# Prototipo_2_1.net
KiCad netlist of a schematic drawn in EAGLE
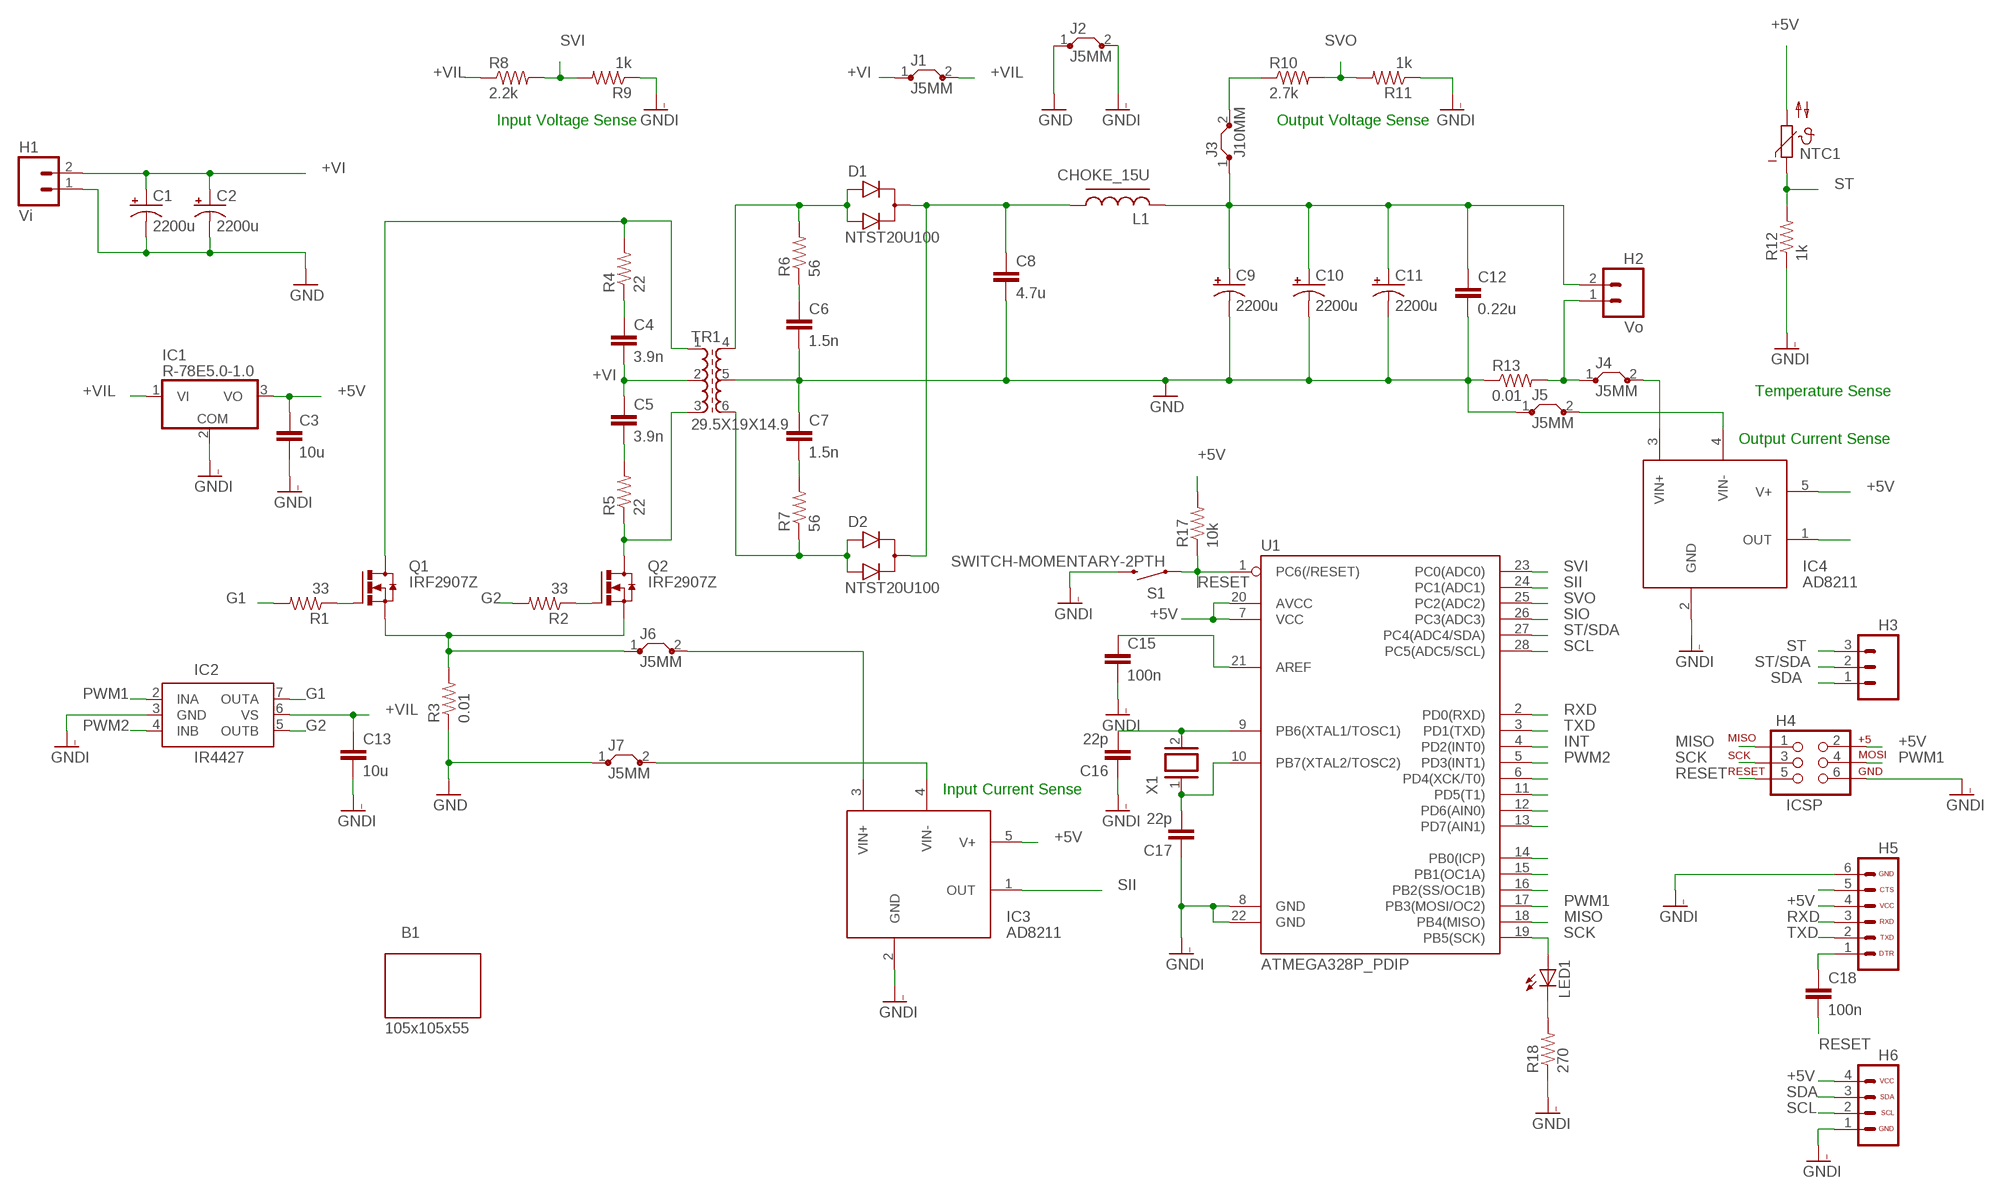
[diagram p0: schematic, sheet 1]

(export (version "E")
  (design (tool "Eeschema 10.0.6"))
  (components
    (comp (ref "B1")
      (value "105x105x55")
      (footprint "eagle-import:BOX_105X105X55")
      (libsource (lib "eagle-import") (part "BOX_105X105X55"))
    )
    (comp (ref "C1")
      (value "2200u")
      (footprint "eagle-import:CPOL_RADIAL_12.5MM_5MM")
      (libsource (lib "eagle-import") (part "CPOL_12.5MM_5MM"))
    )
    (comp (ref "C2")
      (value "2200u")
      (footprint "eagle-import:CPOL_RADIAL_12.5MM_5MM")
      (libsource (lib "eagle-import") (part "CPOL_12.5MM_5MM"))
    )
    (comp (ref "C3")
      (value "10u")
      (footprint "eagle-import:C5B2.5")
      (libsource (lib "eagle-import") (part "C5/2.5"))
    )
    (comp (ref "C4")
      (value "3.9n")
      (footprint "eagle-import:C7.5B3")
      (libsource (lib "eagle-import") (part "C7.5/3"))
    )
    (comp (ref "C5")
      (value "3.9n")
      (footprint "eagle-import:C7.5B3")
      (libsource (lib "eagle-import") (part "C7.5/3"))
    )
    (comp (ref "C6")
      (value "1.5n")
      (footprint "eagle-import:C7.5B3")
      (libsource (lib "eagle-import") (part "C7.5/3"))
    )
    (comp (ref "C7")
      (value "1.5n")
      (footprint "eagle-import:C7.5B3")
      (libsource (lib "eagle-import") (part "C7.5/3"))
    )
    (comp (ref "C8")
      (value "4.7u")
      (footprint "eagle-import:C5B2.5")
      (libsource (lib "eagle-import") (part "C5/2.5"))
    )
    (comp (ref "C9")
      (value "2200u")
      (footprint "eagle-import:CPOL_RADIAL_12.5MM_5MM")
      (libsource (lib "eagle-import") (part "CPOL_12.5MM_5MM"))
    )
    (comp (ref "C10")
      (value "2200u")
      (footprint "eagle-import:CPOL_RADIAL_12.5MM_5MM")
      (libsource (lib "eagle-import") (part "CPOL_12.5MM_5MM"))
    )
    (comp (ref "C11")
      (value "2200u")
      (footprint "eagle-import:CPOL_RADIAL_12.5MM_5MM")
      (libsource (lib "eagle-import") (part "CPOL_12.5MM_5MM"))
    )
    (comp (ref "C12")
      (value "0.22u")
      (footprint "eagle-import:C5B3")
      (libsource (lib "eagle-import") (part "C5/3"))
    )
    (comp (ref "C13")
      (value "10u")
      (footprint "eagle-import:C5B2.5")
      (libsource (lib "eagle-import") (part "C5/2.5"))
    )
    (comp (ref "C15")
      (value "100n")
      (footprint "eagle-import:C5B3")
      (libsource (lib "eagle-import") (part "C5/3"))
    )
    (comp (ref "C16")
      (value "22p")
      (footprint "eagle-import:C5B2.5")
      (libsource (lib "eagle-import") (part "C5/2.5"))
    )
    (comp (ref "C17")
      (value "22p")
      (footprint "eagle-import:C5B2.5")
      (libsource (lib "eagle-import") (part "C5/2.5"))
    )
    (comp (ref "C18")
      (value "100n")
      (footprint "eagle-import:C5B3")
      (libsource (lib "eagle-import") (part "C5/3"))
    )
    (comp (ref "D1")
      (value "NTST20U100")
      (footprint "eagle-import:TO220V")
      (libsource (lib "eagle-import") (part "NTST20U100CTG"))
    )
    (comp (ref "D2")
      (value "NTST20U100")
      (footprint "eagle-import:TO220V")
      (libsource (lib "eagle-import") (part "NTST20U100CTG"))
    )
    (comp (ref "H1")
      (value "Vi")
      (footprint "eagle-import:SCREWTERMINAL-5MM-2")
      (libsource (lib "eagle-import") (part "M025MM"))
    )
    (comp (ref "H2")
      (value "Vo")
      (footprint "eagle-import:SCREWTERMINAL-5MM-2")
      (libsource (lib "eagle-import") (part "M025MM"))
    )
    (comp (ref "H3")
      (value "M03PTH")
      (footprint "eagle-import:1X03")
      (libsource (lib "eagle-import") (part "M03PTH"))
    )
    (comp (ref "H4")
      (value "ICSP")
      (footprint "eagle-import:2X3")
      (libsource (lib "eagle-import") (part "AVR_SPI_PRG_6PTH"))
    )
    (comp (ref "H5")
      (value "HEADER_SERIAL")
      (footprint "eagle-import:HEADER_SERIAL")
      (libsource (lib "eagle-import") (part "HEADER_SERIAL"))
    )
    (comp (ref "H6")
      (value "HEADER_I2C")
      (footprint "eagle-import:HEADER_I2C")
      (libsource (lib "eagle-import") (part "HEADER_I2C"))
    )
    (comp (ref "IC1")
      (value "R-78E5.0-1.0")
      (footprint "eagle-import:R-78E5.0-1.0")
      (libsource (lib "eagle-import") (part "R-78E5.0-1.0"))
    )
    (comp (ref "IC2")
      (value "IR4427")
      (footprint "eagle-import:DIL08")
      (libsource (lib "eagle-import") (part "IR4427"))
    )
    (comp (ref "IC3")
      (value "AD8211")
      (footprint "eagle-import:RJ-5")
      (libsource (lib "eagle-import") (part "AD8211"))
    )
    (comp (ref "IC4")
      (value "AD8211")
      (footprint "eagle-import:RJ-5")
      (libsource (lib "eagle-import") (part "AD8211"))
    )
    (comp (ref "J1")
      (value "J5MM")
      (footprint "eagle-import:05")
      (libsource (lib "eagle-import") (part "J5MM"))
    )
    (comp (ref "J2")
      (value "J5MM")
      (footprint "eagle-import:05")
      (libsource (lib "eagle-import") (part "J5MM"))
    )
    (comp (ref "J3")
      (value "J10MM")
      (footprint "eagle-import:10")
      (libsource (lib "eagle-import") (part "J10MM"))
    )
    (comp (ref "J4")
      (value "J5MM")
      (footprint "eagle-import:05")
      (libsource (lib "eagle-import") (part "J5MM"))
    )
    (comp (ref "J5")
      (value "J5MM")
      (footprint "eagle-import:05")
      (libsource (lib "eagle-import") (part "J5MM"))
    )
    (comp (ref "J6")
      (value "J5MM")
      (footprint "eagle-import:05")
      (libsource (lib "eagle-import") (part "J5MM"))
    )
    (comp (ref "J7")
      (value "J5MM")
      (footprint "eagle-import:05")
      (libsource (lib "eagle-import") (part "J5MM"))
    )
    (comp (ref "L1")
      (value "CHOKE_15U")
      (footprint "eagle-import:CHOKE_15U")
      (libsource (lib "eagle-import") (part "CHOKE_15U"))
    )
    (comp (ref "LED1")
      (value "LED5MM")
      (footprint "eagle-import:LED5MM")
      (libsource (lib "eagle-import") (part "LED5MM"))
    )
    (comp (ref "NTC1")
      (value "NTC640")
      (footprint "eagle-import:P640")
      (fields (field (name "OC_FARNELL") "unknown") (field (name "OC_NEWARK") "unknown"))
      (libsource (lib "eagle-import") (part "NTC640"))
    )
    (comp (ref "Q1")
      (value "IRF2907Z")
      (footprint "eagle-import:TO220V")
      (libsource (lib "eagle-import") (part "IRF2907Z"))
    )
    (comp (ref "Q2")
      (value "IRF2907Z")
      (footprint "eagle-import:TO220V")
      (libsource (lib "eagle-import") (part "IRF2907Z"))
    )
    (comp (ref "R1")
      (value "33")
      (footprint "eagle-import:AXIAL-0.4")
      (libsource (lib "eagle-import") (part "RESISTORPTH-1/4W"))
    )
    (comp (ref "R2")
      (value "33")
      (footprint "eagle-import:AXIAL-0.4")
      (libsource (lib "eagle-import") (part "RESISTORPTH-1/4W"))
    )
    (comp (ref "R3")
      (value "0.01")
      (footprint "eagle-import:RSENSE")
      (libsource (lib "eagle-import") (part "RSENSE"))
    )
    (comp (ref "R4")
      (value "22")
      (footprint "eagle-import:AXIAL-0.5")
      (libsource (lib "eagle-import") (part "RESISTORPTH-1/2W"))
    )
    (comp (ref "R5")
      (value "22")
      (footprint "eagle-import:AXIAL-0.5")
      (libsource (lib "eagle-import") (part "RESISTORPTH-1/2W"))
    )
    (comp (ref "R6")
      (value "56")
      (footprint "eagle-import:AXIAL-0.5")
      (libsource (lib "eagle-import") (part "RESISTORPTH-1/2W"))
    )
    (comp (ref "R7")
      (value "56")
      (footprint "eagle-import:AXIAL-0.5")
      (libsource (lib "eagle-import") (part "RESISTORPTH-1/2W"))
    )
    (comp (ref "R8")
      (value "2.2k")
      (footprint "eagle-import:AXIAL-0.4")
      (libsource (lib "eagle-import") (part "RESISTORPTH-1/4W"))
    )
    (comp (ref "R9")
      (value "1k")
      (footprint "eagle-import:AXIAL-0.4")
      (libsource (lib "eagle-import") (part "RESISTORPTH-1/4W"))
    )
    (comp (ref "R10")
      (value "2.7k")
      (footprint "eagle-import:AXIAL-0.4")
      (libsource (lib "eagle-import") (part "RESISTORPTH-1/4W"))
    )
    (comp (ref "R11")
      (value "1k")
      (footprint "eagle-import:AXIAL-0.4")
      (libsource (lib "eagle-import") (part "RESISTORPTH-1/4W"))
    )
    (comp (ref "R12")
      (value "1k")
      (footprint "eagle-import:AXIAL-0.4")
      (libsource (lib "eagle-import") (part "RESISTORPTH-1/4W"))
    )
    (comp (ref "R13")
      (value "0.01")
      (footprint "eagle-import:RSENSE")
      (libsource (lib "eagle-import") (part "RSENSE"))
    )
    (comp (ref "R17")
      (value "10k")
      (footprint "eagle-import:AXIAL-0.4")
      (libsource (lib "eagle-import") (part "RESISTORPTH-1/4W"))
    )
    (comp (ref "R18")
      (value "270")
      (footprint "eagle-import:AXIAL-0.4")
      (libsource (lib "eagle-import") (part "RESISTORPTH-1/4W"))
    )
    (comp (ref "S1")
      (value "SWITCH-MOMENTARY-2PTH")
      (footprint "eagle-import:TACTILE-PTH")
      (libsource (lib "eagle-import") (part "SWITCH-MOMENTARY-2PTH"))
    )
    (comp (ref "TR1")
      (value "29.5X19X14.9")
      (footprint "eagle-import:CORE_29.5X19X14.9")
      (libsource (lib "eagle-import") (part "29.5X19X14.9_N87"))
    )
    (comp (ref "U1")
      (value "ATMEGA328P_PDIP")
      (footprint "eagle-import:DIL28-3")
      (libsource (lib "eagle-import") (part "ATMEGA328P_PDIP"))
    )
    (comp (ref "X1")
      (value "XTAL/S")
      (footprint "eagle-import:QS")
      (libsource (lib "eagle-import") (part "XTAL/S"))
    )
  )
  (nets
    (net (code "1") (name "/+5V") (class "Default")
      (node (ref "C3") (pin "1") (pinfunction "1_1") (pintype "passive"))
      (node (ref "H4") (pin "2") (pinfunction "2_2") (pintype "passive"))
      (node (ref "H5") (pin "4") (pinfunction "4_VCC_4") (pintype "passive"))
      (node (ref "H6") (pin "4") (pinfunction "4_VCC_4") (pintype "passive"))
      (node (ref "IC1") (pin "3") (pinfunction "VO_3") (pintype "power_in"))
      (node (ref "IC3") (pin "5") (pinfunction "V+_5") (pintype "bidirectional"))
      (node (ref "IC4") (pin "5") (pinfunction "V+_5") (pintype "bidirectional"))
      (node (ref "NTC1") (pin "2") (pinfunction "2_2") (pintype "passive"))
      (node (ref "R17") (pin "P$2") (pinfunction "2_P$2") (pintype "passive"))
      (node (ref "U1") (pin "20") (pinfunction "AVCC_20") (pintype "bidirectional"))
      (node (ref "U1") (pin "7") (pinfunction "VCC_7") (pintype "bidirectional"))
    )
    (net (code "2") (name "/+VI") (class "Default")
      (node (ref "C1") (pin "+") (pinfunction "+_+") (pintype "passive"))
      (node (ref "C2") (pin "+") (pinfunction "+_+") (pintype "passive"))
      (node (ref "C4") (pin "2") (pinfunction "2_2") (pintype "passive"))
      (node (ref "C5") (pin "1") (pinfunction "1_1") (pintype "passive"))
      (node (ref "H1") (pin "2") (pinfunction "2_2") (pintype "passive"))
      (node (ref "J1") (pin "1") (pinfunction "1_1") (pintype "passive"))
      (node (ref "TR1") (pin "2") (pinfunction "2_2") (pintype "passive"))
    )
    (net (code "3") (name "/+VIL") (class "Default")
      (node (ref "C13") (pin "1") (pinfunction "1_1") (pintype "passive"))
      (node (ref "IC1") (pin "1") (pinfunction "VI_1") (pintype "power_in"))
      (node (ref "IC2") (pin "6") (pinfunction "VS_6") (pintype "bidirectional"))
      (node (ref "J1") (pin "2") (pinfunction "2_2") (pintype "passive"))
      (node (ref "R8") (pin "P$1") (pinfunction "1_P$1") (pintype "passive"))
    )
    (net (code "4") (name "/G1") (class "Default")
      (node (ref "IC2") (pin "7") (pinfunction "OUTA_7") (pintype "bidirectional"))
      (node (ref "R1") (pin "P$2") (pinfunction "2_P$2") (pintype "passive"))
    )
    (net (code "5") (name "/G2") (class "Default")
      (node (ref "IC2") (pin "5") (pinfunction "OUTB_5") (pintype "bidirectional"))
      (node (ref "R2") (pin "P$2") (pinfunction "2_P$2") (pintype "passive"))
    )
    (net (code "6") (name "/INT") (class "Default")
      (node (ref "U1") (pin "4") (pinfunction "PD2(INT0)_4") (pintype "bidirectional"))
    )
    (net (code "7") (name "/MISO") (class "Default")
      (node (ref "H4") (pin "1") (pinfunction "1_1") (pintype "passive"))
      (node (ref "U1") (pin "18") (pinfunction "PB4(MISO)_18") (pintype "bidirectional"))
    )
    (net (code "8") (name "/PWM1") (class "Default")
      (node (ref "H4") (pin "4") (pinfunction "4_4") (pintype "passive"))
      (node (ref "IC2") (pin "2") (pinfunction "INA_2") (pintype "bidirectional"))
      (node (ref "U1") (pin "17") (pinfunction "PB3(MOSI/OC2)_17") (pintype "bidirectional"))
    )
    (net (code "9") (name "/PWM2") (class "Default")
      (node (ref "IC2") (pin "4") (pinfunction "INB_4") (pintype "bidirectional"))
      (node (ref "U1") (pin "5") (pinfunction "PD3(INT1)_5") (pintype "bidirectional"))
    )
    (net (code "10") (name "/RESET") (class "Default")
      (node (ref "C18") (pin "2") (pinfunction "2_2") (pintype "passive"))
      (node (ref "H4") (pin "5") (pinfunction "5_5") (pintype "passive"))
      (node (ref "R17") (pin "P$1") (pinfunction "1_P$1") (pintype "passive"))
      (node (ref "S1") (pin "1") (pinfunction "1_1") (pintype "passive"))
      (node (ref "U1") (pin "1") (pinfunction "PC6(/RESET)_1") (pintype "bidirectional"))
    )
    (net (code "11") (name "/RXD") (class "Default")
      (node (ref "H5") (pin "3") (pinfunction "3_RXD_3") (pintype "passive"))
      (node (ref "U1") (pin "2") (pinfunction "PD0(RXD)_2") (pintype "bidirectional"))
    )
    (net (code "12") (name "/SCK") (class "Default")
      (node (ref "H4") (pin "3") (pinfunction "3_3") (pintype "passive"))
      (node (ref "LED1") (pin "A") (pinfunction "A_A") (pintype "passive"))
      (node (ref "U1") (pin "19") (pinfunction "PB5(SCK)_19") (pintype "bidirectional"))
    )
    (net (code "13") (name "/SCL") (class "Default")
      (node (ref "H6") (pin "2") (pinfunction "2_SCL_2") (pintype "passive"))
      (node (ref "U1") (pin "28") (pinfunction "PC5(ADC5/SCL)_28") (pintype "bidirectional"))
    )
    (net (code "14") (name "/SDA") (class "Default")
      (node (ref "H3") (pin "1") (pinfunction "1_1") (pintype "passive"))
      (node (ref "H6") (pin "3") (pinfunction "3_SDA_3") (pintype "passive"))
    )
    (net (code "15") (name "/SII") (class "Default")
      (node (ref "IC3") (pin "1") (pinfunction "OUT_1") (pintype "bidirectional"))
      (node (ref "U1") (pin "24") (pinfunction "PC1(ADC1)_24") (pintype "bidirectional"))
    )
    (net (code "16") (name "/SIO") (class "Default")
      (node (ref "IC4") (pin "1") (pinfunction "OUT_1") (pintype "bidirectional"))
      (node (ref "U1") (pin "26") (pinfunction "PC3(ADC3)_26") (pintype "bidirectional"))
    )
    (net (code "17") (name "/ST") (class "Default")
      (node (ref "H3") (pin "3") (pinfunction "3_3") (pintype "passive"))
      (node (ref "NTC1") (pin "1") (pinfunction "1_1") (pintype "passive"))
      (node (ref "R12") (pin "P$2") (pinfunction "2_P$2") (pintype "passive"))
    )
    (net (code "18") (name "/ST{slash}SDA") (class "Default")
      (node (ref "H3") (pin "2") (pinfunction "2_2") (pintype "passive"))
      (node (ref "U1") (pin "27") (pinfunction "PC4(ADC4/SDA)_27") (pintype "bidirectional"))
    )
    (net (code "19") (name "/SVI") (class "Default")
      (node (ref "R8") (pin "P$2") (pinfunction "2_P$2") (pintype "passive"))
      (node (ref "R9") (pin "P$2") (pinfunction "2_P$2") (pintype "passive"))
      (node (ref "U1") (pin "23") (pinfunction "PC0(ADC0)_23") (pintype "bidirectional"))
    )
    (net (code "20") (name "/SVO") (class "Default")
      (node (ref "R10") (pin "P$2") (pinfunction "2_P$2") (pintype "passive"))
      (node (ref "R11") (pin "P$2") (pinfunction "2_P$2") (pintype "passive"))
      (node (ref "U1") (pin "25") (pinfunction "PC2(ADC2)_25") (pintype "bidirectional"))
    )
    (net (code "21") (name "/TXD") (class "Default")
      (node (ref "H5") (pin "2") (pinfunction "2_TXD_2") (pintype "passive"))
      (node (ref "U1") (pin "3") (pinfunction "PD1(TXD)_3") (pintype "bidirectional"))
    )
    (net (code "22") (name "GND") (class "Default")
      (node (ref "C1") (pin "-") (pinfunction "-_-") (pintype "passive"))
      (node (ref "C10") (pin "-") (pinfunction "-_-") (pintype "passive"))
      (node (ref "C11") (pin "-") (pinfunction "-_-") (pintype "passive"))
      (node (ref "C12") (pin "2") (pinfunction "2_2") (pintype "passive"))
      (node (ref "C2") (pin "-") (pinfunction "-_-") (pintype "passive"))
      (node (ref "C6") (pin "2") (pinfunction "2_2") (pintype "passive"))
      (node (ref "C7") (pin "1") (pinfunction "1_1") (pintype "passive"))
      (node (ref "C8") (pin "2") (pinfunction "2_2") (pintype "passive"))
      (node (ref "C9") (pin "-") (pinfunction "-_-") (pintype "passive"))
      (node (ref "H1") (pin "1") (pinfunction "1_1") (pintype "passive"))
      (node (ref "J2") (pin "1") (pinfunction "1_1") (pintype "passive"))
      (node (ref "J5") (pin "1") (pinfunction "1_1") (pintype "passive"))
      (node (ref "J7") (pin "1") (pinfunction "1_1") (pintype "passive"))
      (node (ref "R13") (pin "P$1") (pinfunction "1_P$1") (pintype "passive"))
      (node (ref "R3") (pin "P$1") (pinfunction "1_P$1") (pintype "passive"))
      (node (ref "TR1") (pin "5") (pinfunction "5_5") (pintype "passive"))
    )
    (net (code "23") (name "GNDI") (class "Default")
      (node (ref "C13") (pin "2") (pinfunction "2_2") (pintype "passive"))
      (node (ref "C15") (pin "2") (pinfunction "2_2") (pintype "passive"))
      (node (ref "C16") (pin "1") (pinfunction "1_1") (pintype "passive"))
      (node (ref "C17") (pin "1") (pinfunction "1_1") (pintype "passive"))
      (node (ref "C3") (pin "2") (pinfunction "2_2") (pintype "passive"))
      (node (ref "H4") (pin "6") (pinfunction "6_6") (pintype "passive"))
      (node (ref "H5") (pin "6") (pinfunction "6_GND_6") (pintype "passive"))
      (node (ref "H6") (pin "1") (pinfunction "1_GND_1") (pintype "passive"))
      (node (ref "IC1") (pin "2") (pinfunction "COM_2") (pintype "power_in"))
      (node (ref "IC2") (pin "3") (pinfunction "GND_3") (pintype "bidirectional"))
      (node (ref "IC3") (pin "2") (pinfunction "GND_2") (pintype "bidirectional"))
      (node (ref "IC4") (pin "2") (pinfunction "GND_2") (pintype "bidirectional"))
      (node (ref "J2") (pin "2") (pinfunction "2_2") (pintype "passive"))
      (node (ref "R11") (pin "P$1") (pinfunction "1_P$1") (pintype "passive"))
      (node (ref "R12") (pin "P$1") (pinfunction "1_P$1") (pintype "passive"))
      (node (ref "R18") (pin "P$1") (pinfunction "1_P$1") (pintype "passive"))
      (node (ref "R9") (pin "P$1") (pinfunction "1_P$1") (pintype "passive"))
      (node (ref "S1") (pin "3") (pinfunction "2_3") (pintype "passive"))
      (node (ref "U1") (pin "22") (pinfunction "GND_22") (pintype "bidirectional"))
      (node (ref "U1") (pin "8") (pinfunction "GND_8") (pintype "bidirectional"))
    )
    (net (code "24") (name "Net-(C10-Pad+)") (class "Default")
      (node (ref "C10") (pin "+") (pinfunction "+_+") (pintype "passive"))
      (node (ref "C11") (pin "+") (pinfunction "+_+") (pintype "passive"))
      (node (ref "C12") (pin "1") (pinfunction "1_1") (pintype "passive"))
      (node (ref "C9") (pin "+") (pinfunction "+_+") (pintype "passive"))
      (node (ref "H2") (pin "2") (pinfunction "2_2") (pintype "passive"))
      (node (ref "J3") (pin "1") (pinfunction "1_1") (pintype "passive"))
      (node (ref "L1") (pin "2") (pinfunction "2_2") (pintype "passive"))
    )
    (net (code "25") (name "Net-(D1-A1)") (class "Default")
      (node (ref "D1") (pin "1") (pinfunction "A1_1") (pintype "passive"))
      (node (ref "D1") (pin "3") (pinfunction "A2_3") (pintype "passive"))
      (node (ref "R6") (pin "P$2") (pinfunction "2_P$2") (pintype "passive"))
      (node (ref "TR1") (pin "4") (pinfunction "4_4") (pintype "passive"))
    )
    (net (code "26") (name "Net-(D1-C)") (class "Default")
      (node (ref "C8") (pin "1") (pinfunction "1_1") (pintype "passive"))
      (node (ref "D1") (pin "2") (pinfunction "C_2") (pintype "passive"))
      (node (ref "D2") (pin "2") (pinfunction "C_2") (pintype "passive"))
      (node (ref "L1") (pin "1") (pinfunction "1_1") (pintype "passive"))
    )
    (net (code "27") (name "Net-(D2-A1)") (class "Default")
      (node (ref "D2") (pin "1") (pinfunction "A1_1") (pintype "passive"))
      (node (ref "D2") (pin "3") (pinfunction "A2_3") (pintype "passive"))
      (node (ref "R7") (pin "P$1") (pinfunction "1_P$1") (pintype "passive"))
      (node (ref "TR1") (pin "6") (pinfunction "6_6") (pintype "passive"))
    )
    (net (code "28") (name "Net-(H5-1_DTR)") (class "Default")
      (node (ref "C18") (pin "1") (pinfunction "1_1") (pintype "passive"))
      (node (ref "H5") (pin "1") (pinfunction "1_DTR_1") (pintype "passive"))
    )
    (net (code "29") (name "Net-(IC3-VIN+)") (class "Default")
      (node (ref "IC3") (pin "3") (pinfunction "VIN+_3") (pintype "bidirectional"))
      (node (ref "J6") (pin "2") (pinfunction "2_2") (pintype "passive"))
    )
    (net (code "30") (name "Net-(IC3-VIN-)") (class "Default")
      (node (ref "IC3") (pin "4") (pinfunction "VIN-_4") (pintype "bidirectional"))
      (node (ref "J7") (pin "2") (pinfunction "2_2") (pintype "passive"))
    )
    (net (code "31") (name "Net-(IC4-VIN+)") (class "Default")
      (node (ref "IC4") (pin "3") (pinfunction "VIN+_3") (pintype "bidirectional"))
      (node (ref "J4") (pin "2") (pinfunction "2_2") (pintype "passive"))
    )
    (net (code "32") (name "Net-(IC4-VIN-)") (class "Default")
      (node (ref "IC4") (pin "4") (pinfunction "VIN-_4") (pintype "bidirectional"))
      (node (ref "J5") (pin "2") (pinfunction "2_2") (pintype "passive"))
    )
    (net (code "33") (name "Net-(LED1-C)") (class "Default")
      (node (ref "LED1") (pin "K") (pinfunction "C_K") (pintype "passive"))
      (node (ref "R18") (pin "P$2") (pinfunction "2_P$2") (pintype "passive"))
    )
    (net (code "34") (name "Net-(Q1-D)") (class "Default")
      (node (ref "Q1") (pin "2") (pinfunction "D_2") (pintype "passive"))
      (node (ref "R4") (pin "P$2") (pinfunction "2_P$2") (pintype "passive"))
      (node (ref "TR1") (pin "1") (pinfunction "1_1") (pintype "passive"))
    )
    (net (code "35") (name "Net-(Q1-G)") (class "Default")
      (node (ref "Q1") (pin "1") (pinfunction "G_1") (pintype "passive"))
      (node (ref "R1") (pin "P$1") (pinfunction "1_P$1") (pintype "passive"))
    )
    (net (code "36") (name "Net-(Q1-S)") (class "Default")
      (node (ref "J6") (pin "1") (pinfunction "1_1") (pintype "passive"))
      (node (ref "Q1") (pin "3") (pinfunction "S_3") (pintype "passive"))
      (node (ref "Q2") (pin "3") (pinfunction "S_3") (pintype "passive"))
      (node (ref "R3") (pin "P$2") (pinfunction "2_P$2") (pintype "passive"))
    )
    (net (code "37") (name "Net-(Q2-D)") (class "Default")
      (node (ref "Q2") (pin "2") (pinfunction "D_2") (pintype "passive"))
      (node (ref "R5") (pin "P$1") (pinfunction "1_P$1") (pintype "passive"))
      (node (ref "TR1") (pin "3") (pinfunction "3_3") (pintype "passive"))
    )
    (net (code "38") (name "Net-(Q2-G)") (class "Default")
      (node (ref "Q2") (pin "1") (pinfunction "G_1") (pintype "passive"))
      (node (ref "R2") (pin "P$1") (pinfunction "1_P$1") (pintype "passive"))
    )
    (net (code "39") (name "Net-(R4-1)") (class "Default")
      (node (ref "C4") (pin "1") (pinfunction "1_1") (pintype "passive"))
      (node (ref "R4") (pin "P$1") (pinfunction "1_P$1") (pintype "passive"))
    )
    (net (code "40") (name "Net-(R5-2)") (class "Default")
      (node (ref "C5") (pin "2") (pinfunction "2_2") (pintype "passive"))
      (node (ref "R5") (pin "P$2") (pinfunction "2_P$2") (pintype "passive"))
    )
    (net (code "41") (name "Net-(R6-1)") (class "Default")
      (node (ref "C6") (pin "1") (pinfunction "1_1") (pintype "passive"))
      (node (ref "R6") (pin "P$1") (pinfunction "1_P$1") (pintype "passive"))
    )
    (net (code "42") (name "Net-(R7-2)") (class "Default")
      (node (ref "C7") (pin "2") (pinfunction "2_2") (pintype "passive"))
      (node (ref "R7") (pin "P$2") (pinfunction "2_P$2") (pintype "passive"))
    )
    (net (code "43") (name "Net-(R10-1)") (class "Default")
      (node (ref "J3") (pin "2") (pinfunction "2_2") (pintype "passive"))
      (node (ref "R10") (pin "P$1") (pinfunction "1_P$1") (pintype "passive"))
    )
    (net (code "44") (name "Net-(R13-2)") (class "Default")
      (node (ref "H2") (pin "1") (pinfunction "1_1") (pintype "passive"))
      (node (ref "J4") (pin "1") (pinfunction "1_1") (pintype "passive"))
      (node (ref "R13") (pin "P$2") (pinfunction "2_P$2") (pintype "passive"))
    )
    (net (code "45") (name "Net-(U1-AREF)") (class "Default")
      (node (ref "C15") (pin "1") (pinfunction "1_1") (pintype "passive"))
      (node (ref "U1") (pin "21") (pinfunction "AREF_21") (pintype "bidirectional"))
    )
    (net (code "46") (name "Net-(U1-PB6(XTAL1{slash}TOSC1))") (class "Default")
      (node (ref "C16") (pin "2") (pinfunction "2_2") (pintype "passive"))
      (node (ref "U1") (pin "9") (pinfunction "PB6(XTAL1/TOSC1)_9") (pintype "bidirectional"))
      (node (ref "X1") (pin "2") (pinfunction "2_2") (pintype "passive"))
    )
    (net (code "47") (name "Net-(U1-PB7(XTAL2{slash}TOSC2))") (class "Default")
      (node (ref "C17") (pin "2") (pinfunction "2_2") (pintype "passive"))
      (node (ref "U1") (pin "10") (pinfunction "PB7(XTAL2/TOSC2)_10") (pintype "bidirectional"))
      (node (ref "X1") (pin "1") (pinfunction "1_1") (pintype "passive"))
    )
    (net (code "48") (name "unconnected-(H5-5_CTS-Pad5)") (class "Default")
      (node (ref "H5") (pin "5") (pinfunction "5_CTS_5") (pintype "passive"))
    )
    (net (code "49") (name "unconnected-(U1-PB0(ICP)-Pad14)") (class "Default")
      (node (ref "U1") (pin "14") (pinfunction "PB0(ICP)_14") (pintype "bidirectional"))
    )
    (net (code "50") (name "unconnected-(U1-PB1(OC1A)-Pad15)") (class "Default")
      (node (ref "U1") (pin "15") (pinfunction "PB1(OC1A)_15") (pintype "bidirectional"))
    )
    (net (code "51") (name "unconnected-(U1-PB2(SS{slash}OC1B)-Pad16)") (class "Default")
      (node (ref "U1") (pin "16") (pinfunction "PB2(SS/OC1B)_16") (pintype "bidirectional"))
    )
    (net (code "52") (name "unconnected-(U1-PD4(XCK{slash}T0)-Pad6)") (class "Default")
      (node (ref "U1") (pin "6") (pinfunction "PD4(XCK/T0)_6") (pintype "bidirectional"))
    )
    (net (code "53") (name "unconnected-(U1-PD5(T1)-Pad11)") (class "Default")
      (node (ref "U1") (pin "11") (pinfunction "PD5(T1)_11") (pintype "bidirectional"))
    )
    (net (code "54") (name "unconnected-(U1-PD6(AIN0)-Pad12)") (class "Default")
      (node (ref "U1") (pin "12") (pinfunction "PD6(AIN0)_12") (pintype "bidirectional"))
    )
    (net (code "55") (name "unconnected-(U1-PD7(AIN1)-Pad13)") (class "Default")
      (node (ref "U1") (pin "13") (pinfunction "PD7(AIN1)_13") (pintype "bidirectional"))
    )
  )
)
